# SCH.net
KiCad netlist of a schematic drawn in Altium Designer
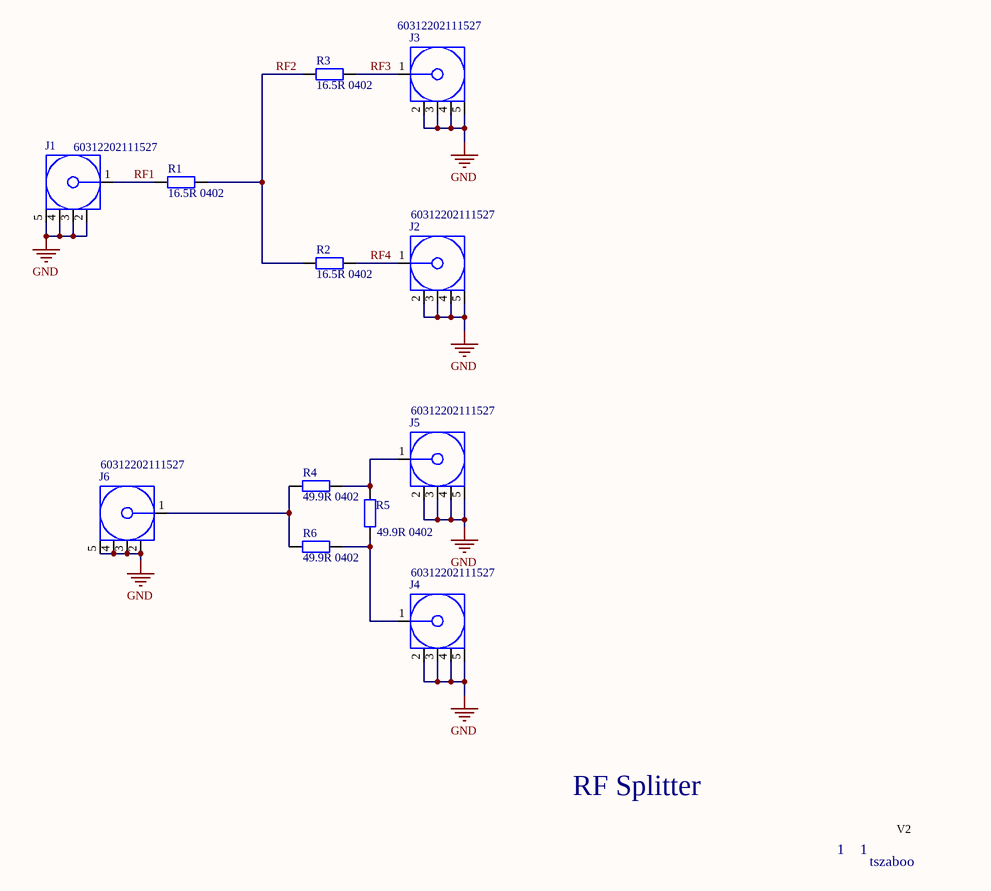
[diagram p0: SCH.SchDoc]

(export (version "E")
  (design (tool "Eeschema 10.0.6"))
  (components
    (comp (ref "J1")
      (value "60312202111527")
      (footprint "60312202111527")
      (description "60312202111527 WR-SMA_SMA PCB End Launch Jack")
      (libsource (lib "Altium Content Vault") (part "Jack_4GND"))
    )
    (comp (ref "J2")
      (value "60312202111527")
      (footprint "60312202111527")
      (description "60312202111527 WR-SMA_SMA PCB End Launch Jack")
      (libsource (lib "Altium Content Vault") (part "Jack_4GND"))
    )
    (comp (ref "J3")
      (value "60312202111527")
      (footprint "60312202111527")
      (description "60312202111527 WR-SMA_SMA PCB End Launch Jack")
      (libsource (lib "Altium Content Vault") (part "Jack_4GND"))
    )
    (comp (ref "J4")
      (value "60312202111527")
      (footprint "60312202111527")
      (description "60312202111527 WR-SMA_SMA PCB End Launch Jack")
      (libsource (lib "Altium Content Vault") (part "Jack_4GND"))
    )
    (comp (ref "J5")
      (value "60312202111527")
      (footprint "60312202111527")
      (description "60312202111527 WR-SMA_SMA PCB End Launch Jack")
      (libsource (lib "Altium Content Vault") (part "Jack_4GND"))
    )
    (comp (ref "J6")
      (value "60312202111527")
      (footprint "60312202111527")
      (description "60312202111527 WR-SMA_SMA PCB End Launch Jack")
      (libsource (lib "Altium Content Vault") (part "Jack_4GND"))
    )
    (comp (ref "R1")
      (value "Res")
      (footprint "RESC0402N")
      (description "RES SMD 16.5 OHM 1% 1/16W 100PPM 0402")
      (fields (field (name "SCH") "16.5R 0402") (field (name "MANUFACTURER") "VISHAY"))
      (libsource (lib "VISHAY CRCW") (part "Res"))
    )
    (comp (ref "R2")
      (value "Res")
      (footprint "RESC0402N")
      (description "RES SMD 16.5 OHM 1% 1/16W 100PPM 0402")
      (fields (field (name "SCH") "16.5R 0402") (field (name "MANUFACTURER") "VISHAY"))
      (libsource (lib "VISHAY CRCW") (part "Res"))
    )
    (comp (ref "R3")
      (value "Res")
      (footprint "RESC0402N")
      (description "RES SMD 16.5 OHM 1% 1/16W 100PPM 0402")
      (fields (field (name "SCH") "16.5R 0402") (field (name "MANUFACTURER") "VISHAY"))
      (libsource (lib "VISHAY CRCW") (part "Res"))
    )
    (comp (ref "R4")
      (value "Res")
      (footprint "RESC0402N")
      (description "RES SMD 49.9 OHM 1% 1/16W 100PPM 0402")
      (fields (field (name "SCH") "49.9R 0402") (field (name "MANUFACTURER") "VISHAY"))
      (libsource (lib "VISHAY CRCW") (part "Res"))
    )
    (comp (ref "R5")
      (value "Res")
      (footprint "RESC0402N")
      (description "RES SMD 49.9 OHM 1% 1/16W 100PPM 0402")
      (fields (field (name "SCH") "49.9R 0402") (field (name "MANUFACTURER") "VISHAY"))
      (libsource (lib "") (part "Res_1"))
    )
    (comp (ref "R6")
      (value "Res")
      (footprint "RESC0402N")
      (description "RES SMD 49.9 OHM 1% 1/16W 100PPM 0402")
      (fields (field (name "SCH") "49.9R 0402") (field (name "MANUFACTURER") "VISHAY"))
      (libsource (lib "VISHAY CRCW") (part "Res"))
    )
  )
  (nets
    (net (code "1") (name "/RF1") (class "Default")
      (node (ref "J1") (pin "1") (pinfunction "Signal_1") (pintype "passive"))
      (node (ref "R1") (pin "1") (pinfunction "1_1") (pintype "passive"))
    )
    (net (code "2") (name "/RF2") (class "Default")
      (node (ref "R1") (pin "2") (pinfunction "2_2") (pintype "passive"))
      (node (ref "R2") (pin "1") (pinfunction "1_1") (pintype "passive"))
      (node (ref "R3") (pin "1") (pinfunction "1_1") (pintype "passive"))
    )
    (net (code "3") (name "/RF3") (class "Default")
      (node (ref "J3") (pin "1") (pinfunction "Signal_1") (pintype "passive"))
      (node (ref "R3") (pin "2") (pinfunction "2_2") (pintype "passive"))
    )
    (net (code "4") (name "/RF4") (class "Default")
      (node (ref "J2") (pin "1") (pinfunction "Signal_1") (pintype "passive"))
      (node (ref "R2") (pin "2") (pinfunction "2_2") (pintype "passive"))
    )
    (net (code "5") (name "GND") (class "Default")
      (node (ref "J1") (pin "2") (pinfunction "GND_2") (pintype "passive"))
      (node (ref "J1") (pin "3") (pinfunction "GND_3") (pintype "passive"))
      (node (ref "J1") (pin "4") (pinfunction "GND_4") (pintype "passive"))
      (node (ref "J1") (pin "5") (pinfunction "GND_5") (pintype "passive"))
      (node (ref "J2") (pin "2") (pinfunction "GND_2") (pintype "passive"))
      (node (ref "J2") (pin "3") (pinfunction "GND_3") (pintype "passive"))
      (node (ref "J2") (pin "4") (pinfunction "GND_4") (pintype "passive"))
      (node (ref "J2") (pin "5") (pinfunction "GND_5") (pintype "passive"))
      (node (ref "J3") (pin "2") (pinfunction "GND_2") (pintype "passive"))
      (node (ref "J3") (pin "3") (pinfunction "GND_3") (pintype "passive"))
      (node (ref "J3") (pin "4") (pinfunction "GND_4") (pintype "passive"))
      (node (ref "J3") (pin "5") (pinfunction "GND_5") (pintype "passive"))
      (node (ref "J4") (pin "2") (pinfunction "GND_2") (pintype "passive"))
      (node (ref "J4") (pin "3") (pinfunction "GND_3") (pintype "passive"))
      (node (ref "J4") (pin "4") (pinfunction "GND_4") (pintype "passive"))
      (node (ref "J4") (pin "5") (pinfunction "GND_5") (pintype "passive"))
      (node (ref "J5") (pin "2") (pinfunction "GND_2") (pintype "passive"))
      (node (ref "J5") (pin "3") (pinfunction "GND_3") (pintype "passive"))
      (node (ref "J5") (pin "4") (pinfunction "GND_4") (pintype "passive"))
      (node (ref "J5") (pin "5") (pinfunction "GND_5") (pintype "passive"))
      (node (ref "J6") (pin "2") (pinfunction "GND_2") (pintype "passive"))
      (node (ref "J6") (pin "3") (pinfunction "GND_3") (pintype "passive"))
      (node (ref "J6") (pin "4") (pinfunction "GND_4") (pintype "passive"))
      (node (ref "J6") (pin "5") (pinfunction "GND_5") (pintype "passive"))
    )
    (net (code "6") (name "Net-(J4-Signal)") (class "Default")
      (node (ref "J4") (pin "1") (pinfunction "Signal_1") (pintype "passive"))
      (node (ref "R5") (pin "1") (pinfunction "1_1") (pintype "passive"))
      (node (ref "R6") (pin "2") (pinfunction "2_2") (pintype "passive"))
    )
    (net (code "7") (name "Net-(J5-Signal)") (class "Default")
      (node (ref "J5") (pin "1") (pinfunction "Signal_1") (pintype "passive"))
      (node (ref "R4") (pin "2") (pinfunction "2_2") (pintype "passive"))
      (node (ref "R5") (pin "2") (pinfunction "2_2") (pintype "passive"))
    )
    (net (code "8") (name "Net-(J6-Signal)") (class "Default")
      (node (ref "J6") (pin "1") (pinfunction "Signal_1") (pintype "passive"))
      (node (ref "R4") (pin "1") (pinfunction "1_1") (pintype "passive"))
      (node (ref "R6") (pin "1") (pinfunction "1_1") (pintype "passive"))
    )
  )
)
